# sch.net
KiCad netlist of a schematic drawn in EasyEDA
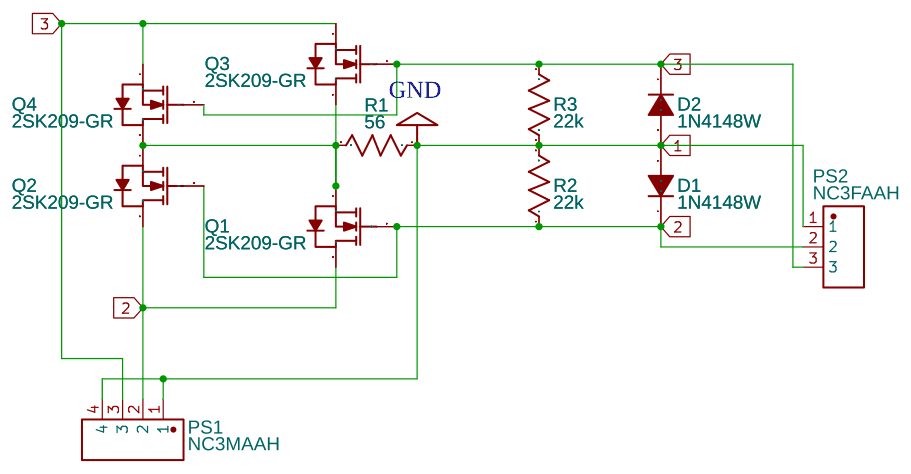
[diagram p0: schematic sheet]

(export (version "E")
  (design (tool "Eeschema 10.0.6"))
  (components
    (comp (ref "D1")
      (value "1N4148W")
      (fields (field (name "Manufacturer") "MDD"))
      (libsource (lib "") (part "1N4148W-C84367_1"))
    )
    (comp (ref "D2")
      (value "1N4148W")
      (fields (field (name "Manufacturer") "MDD"))
      (libsource (lib "") (part "1N4148W-C84367"))
    )
    (comp (ref "PS1")
      (value "NC3MAAH")
      (fields (field (name "Manufacturer") "Neutrik"))
      (libsource (lib "") (part "NC3MAAH"))
    )
    (comp (ref "PS2")
      (value "NC3FAAH")
      (fields (field (name "Manufacturer") "Neutrik"))
      (libsource (lib "") (part "NC3FAAH"))
    )
    (comp (ref "Q1")
      (value "2SK209-GR")
      (fields (field (name "Manufacturer Part") "2SK209-GR(TE85L,F)") (field (name "Manufacturer") "TOSHIBA"))
      (libsource (lib "") (part "2SK209-GR(TE85L,F)"))
    )
    (comp (ref "Q2")
      (value "2SK209-GR")
      (fields (field (name "Manufacturer Part") "2SK209-GR(TE85L,F)") (field (name "Manufacturer") "TOSHIBA"))
      (libsource (lib "") (part "2SK209-GR(TE85L,F)"))
    )
    (comp (ref "Q3")
      (value "2SK209-GR")
      (fields (field (name "Manufacturer Part") "2SK209-GR(TE85L,F)") (field (name "Manufacturer") "TOSHIBA"))
      (libsource (lib "") (part "2SK209-GR(TE85L,F)"))
    )
    (comp (ref "Q4")
      (value "2SK209-GR")
      (fields (field (name "Manufacturer Part") "2SK209-GR(TE85L,F)") (field (name "Manufacturer") "TOSHIBA"))
      (libsource (lib "") (part "2SK209-GR(TE85L,F)"))
    )
    (comp (ref "R1") (value "56") (libsource (lib "") (part "R_0805_US_2")))
    (comp (ref "R2") (value "22k") (libsource (lib "") (part "R_0805_US")))
    (comp (ref "R3") (value "22k") (libsource (lib "") (part "R_0805_US_1")))
  )
  (nets
    (net (code "1") (name "1") (class "Default")
      (node (ref "D1") (pin "2") (pinfunction "A_2") (pintype "unspecified"))
      (node (ref "D2") (pin "2") (pinfunction "A_2") (pintype "unspecified"))
      (node (ref "PS1") (pin "1") (pinfunction "1_1") (pintype "unspecified"))
      (node (ref "PS1") (pin "4") (pinfunction "4_4") (pintype "unspecified"))
      (node (ref "PS2") (pin "1") (pinfunction "1_1") (pintype "unspecified"))
      (node (ref "R1") (pin "1") (pinfunction "1_1") (pintype "unspecified"))
      (node (ref "R2") (pin "2") (pinfunction "2_2") (pintype "unspecified"))
      (node (ref "R3") (pin "2") (pinfunction "2_2") (pintype "unspecified"))
    )
    (net (code "2") (name "2") (class "Default")
      (node (ref "D1") (pin "1") (pinfunction "C_1") (pintype "unspecified"))
      (node (ref "PS1") (pin "2") (pinfunction "2_2") (pintype "unspecified"))
      (node (ref "PS2") (pin "2") (pinfunction "2_2") (pintype "unspecified"))
      (node (ref "Q1") (pin "2") (pinfunction "D_2") (pintype "unspecified"))
      (node (ref "Q1") (pin "3") (pinfunction "G_3") (pintype "unspecified"))
      (node (ref "Q2") (pin "2") (pinfunction "D_2") (pintype "unspecified"))
      (node (ref "Q2") (pin "3") (pinfunction "G_3") (pintype "unspecified"))
      (node (ref "R2") (pin "1") (pinfunction "1_1") (pintype "unspecified"))
    )
    (net (code "3") (name "3") (class "Default")
      (node (ref "D2") (pin "1") (pinfunction "C_1") (pintype "unspecified"))
      (node (ref "PS1") (pin "3") (pinfunction "3_3") (pintype "unspecified"))
      (node (ref "PS2") (pin "3") (pinfunction "3_3") (pintype "unspecified"))
      (node (ref "Q3") (pin "1") (pinfunction "S_1") (pintype "unspecified"))
      (node (ref "Q3") (pin "3") (pinfunction "G_3") (pintype "unspecified"))
      (node (ref "Q4") (pin "1") (pinfunction "S_1") (pintype "unspecified"))
      (node (ref "Q4") (pin "3") (pinfunction "G_3") (pintype "unspecified"))
      (node (ref "R3") (pin "1") (pinfunction "1_1") (pintype "unspecified"))
    )
    (net (code "4") (name "Net-(Q1-S)") (class "Default")
      (node (ref "Q1") (pin "1") (pinfunction "S_1") (pintype "unspecified"))
      (node (ref "Q2") (pin "1") (pinfunction "S_1") (pintype "unspecified"))
      (node (ref "Q3") (pin "2") (pinfunction "D_2") (pintype "unspecified"))
      (node (ref "Q4") (pin "2") (pinfunction "D_2") (pintype "unspecified"))
      (node (ref "R1") (pin "2") (pinfunction "2_2") (pintype "unspecified"))
    )
  )
)
